# LPC11UxxMini.net
KiCad netlist of a schematic drawn in EAGLE
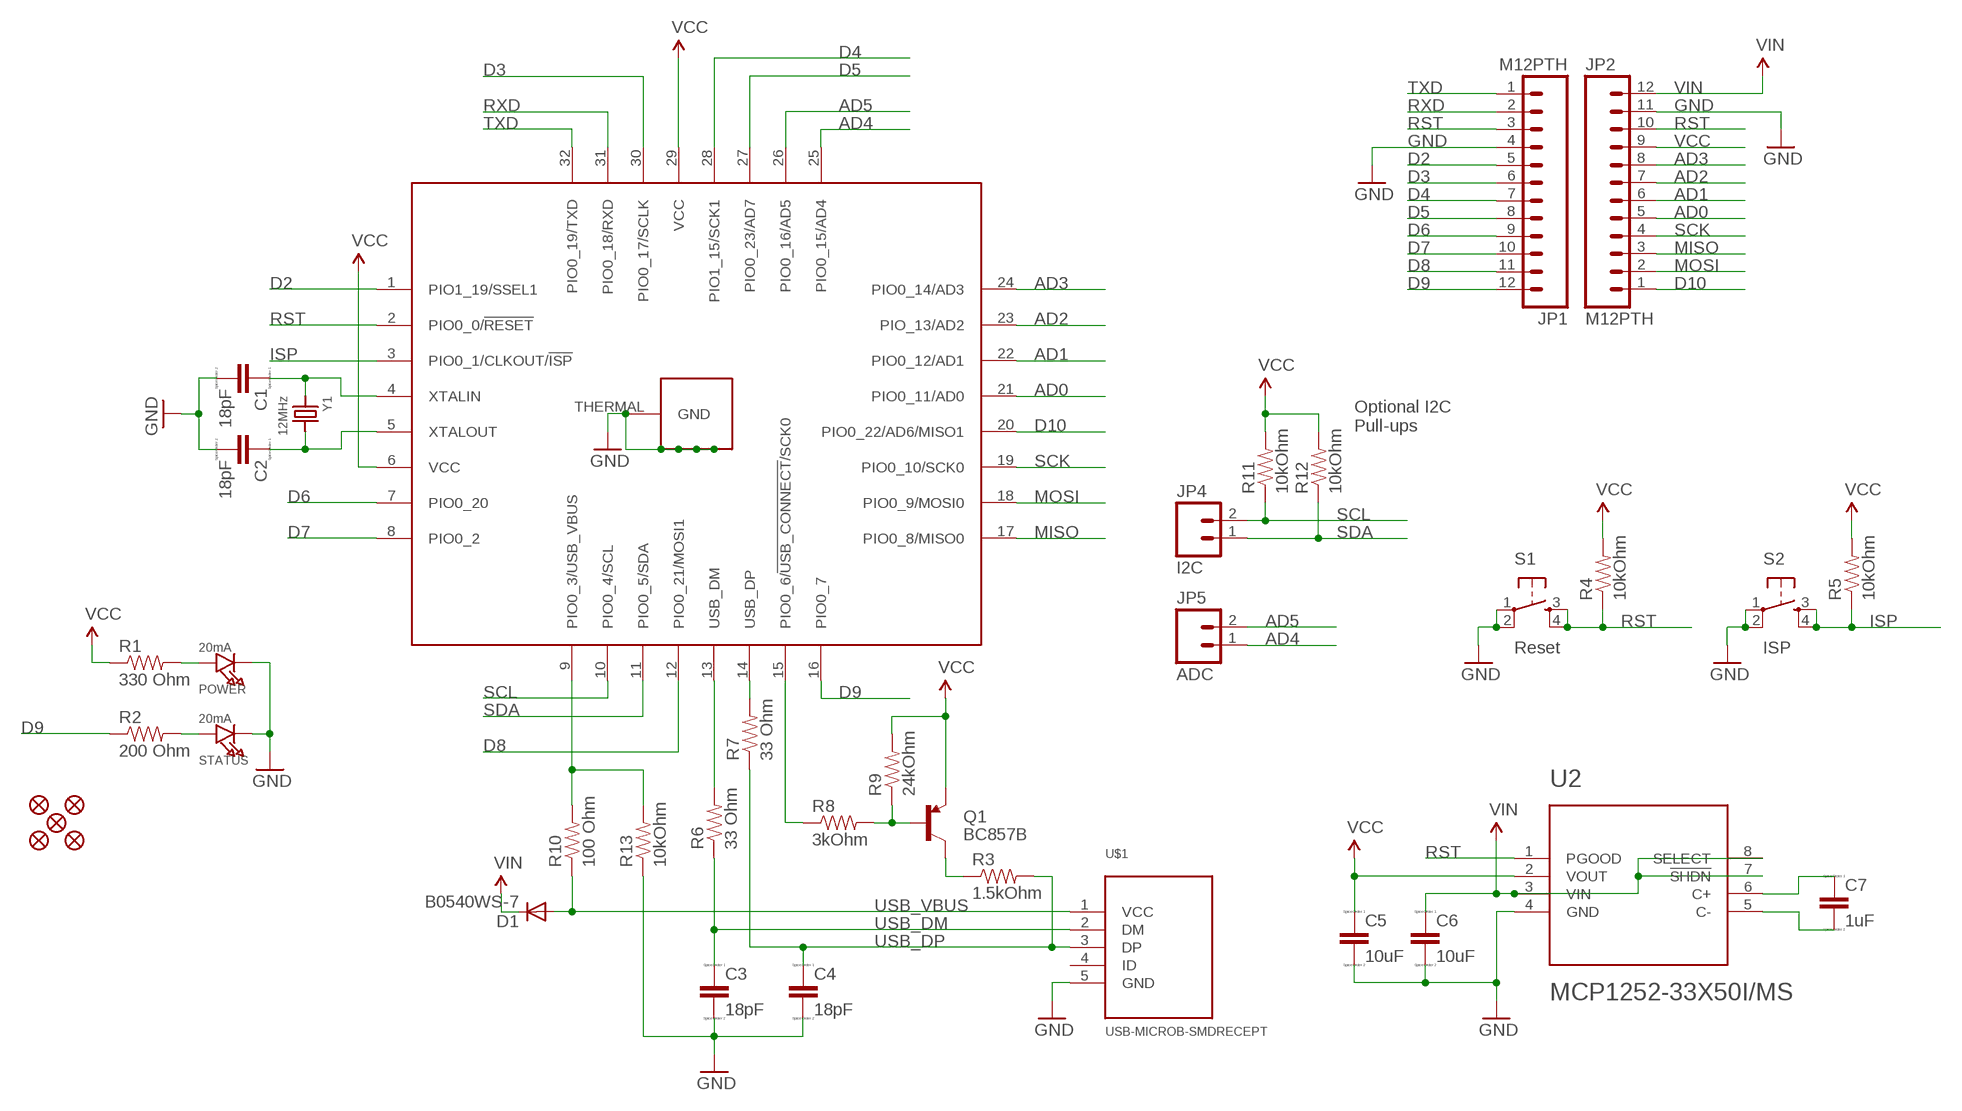
[diagram p0: schematic, sheet 1]

(export (version "E")
  (design (tool "Eeschema 10.0.6"))
  (components
    (comp (ref "C1")
      (value "18pF")
      (footprint "eagle-import:0603-CAP")
      (libsource (lib "eagle-import") (part "CAP0603-CAP"))
    )
    (comp (ref "C2")
      (value "18pF")
      (footprint "eagle-import:0603-CAP")
      (libsource (lib "eagle-import") (part "CAP0603-CAP"))
    )
    (comp (ref "C3")
      (value "18pF")
      (footprint "eagle-import:0603-CAP")
      (libsource (lib "eagle-import") (part "CAP0603-CAP"))
    )
    (comp (ref "C4")
      (value "18pF")
      (footprint "eagle-import:0603-CAP")
      (libsource (lib "eagle-import") (part "CAP0603-CAP"))
    )
    (comp (ref "C5")
      (value "10uF")
      (footprint "eagle-import:1206")
      (libsource (lib "eagle-import") (part "CAP1206"))
    )
    (comp (ref "C6")
      (value "10uF")
      (footprint "eagle-import:1206")
      (libsource (lib "eagle-import") (part "CAP1206"))
    )
    (comp (ref "C7")
      (value "1uF")
      (footprint "eagle-import:0805")
      (libsource (lib "eagle-import") (part "CAP0805"))
    )
    (comp (ref "D1")
      (value "B0540WS-7")
      (footprint "eagle-import:SOD-323")
      (libsource (lib "eagle-import") (part "DIODESOD"))
    )
    (comp (ref "JP1")
      (value "M12PTH")
      (footprint "eagle-import:1X12")
      (libsource (lib "eagle-import") (part "M12PTH"))
    )
    (comp (ref "JP2")
      (value "M12PTH")
      (footprint "eagle-import:1X12")
      (libsource (lib "eagle-import") (part "M12PTH"))
    )
    (comp (ref "JP3")
      (value "FIDUCIALUFIDUCIAL")
      (footprint "eagle-import:MICRO-FIDUCIAL")
      (libsource (lib "eagle-import") (part "FIDUCIALUFIDUCIAL"))
    )
    (comp (ref "JP4")
      (value "I2C")
      (footprint "eagle-import:1X02")
      (libsource (lib "eagle-import") (part "M02PTH"))
    )
    (comp (ref "JP5")
      (value "ADC")
      (footprint "eagle-import:1X02")
      (libsource (lib "eagle-import") (part "M02PTH"))
    )
    (comp (ref "JP6")
      (value "FIDUCIALUFIDUCIAL")
      (footprint "eagle-import:MICRO-FIDUCIAL")
      (libsource (lib "eagle-import") (part "FIDUCIALUFIDUCIAL"))
    )
    (comp (ref "JP7")
      (value "FIDUCIALUFIDUCIAL")
      (footprint "eagle-import:MICRO-FIDUCIAL")
      (libsource (lib "eagle-import") (part "FIDUCIALUFIDUCIAL"))
    )
    (comp (ref "JP8")
      (value "FIDUCIALUFIDUCIAL")
      (footprint "eagle-import:MICRO-FIDUCIAL")
      (libsource (lib "eagle-import") (part "FIDUCIALUFIDUCIAL"))
    )
    (comp (ref "JP9")
      (value "FIDUCIALUFIDUCIAL")
      (footprint "eagle-import:MICRO-FIDUCIAL")
      (libsource (lib "eagle-import") (part "FIDUCIALUFIDUCIAL"))
    )
    (comp (ref "POWER")
      (value "20mA")
      (footprint "eagle-import:CHIPLED_0603_NOOUTLINE")
      (libsource (lib "eagle-import") (part "LED0603_NOOUTLINE"))
    )
    (comp (ref "Q1")
      (value "BC857B")
      (footprint "eagle-import:SOT23-3")
      (libsource (lib "eagle-import") (part "TRANSISTOR_PNPSMD"))
    )
    (comp (ref "R1")
      (value "330 Ohm")
      (footprint "eagle-import:0402-RES")
      (libsource (lib "eagle-import") (part "RESISTOR0402-RES"))
    )
    (comp (ref "R2")
      (value "200 Ohm")
      (footprint "eagle-import:0402-RES")
      (libsource (lib "eagle-import") (part "RESISTOR0402-RES"))
    )
    (comp (ref "R3")
      (value "1.5kOhm")
      (footprint "eagle-import:0402-RES")
      (libsource (lib "eagle-import") (part "RESISTOR0402-RES"))
    )
    (comp (ref "R4")
      (value "10kOhm")
      (footprint "eagle-import:0402-RES")
      (libsource (lib "eagle-import") (part "RESISTOR0402-RES"))
    )
    (comp (ref "R5")
      (value "10kOhm")
      (footprint "eagle-import:0402-RES")
      (libsource (lib "eagle-import") (part "RESISTOR0402-RES"))
    )
    (comp (ref "R6")
      (value "33 Ohm")
      (footprint "eagle-import:0402-RES")
      (libsource (lib "eagle-import") (part "RESISTOR0402-RES"))
    )
    (comp (ref "R7")
      (value "33 Ohm")
      (footprint "eagle-import:0402-RES")
      (libsource (lib "eagle-import") (part "RESISTOR0402-RES"))
    )
    (comp (ref "R8")
      (value "3kOhm")
      (footprint "eagle-import:0402-RES")
      (libsource (lib "eagle-import") (part "RESISTOR0402-RES"))
    )
    (comp (ref "R9")
      (value "24kOhm")
      (footprint "eagle-import:0402-RES")
      (libsource (lib "eagle-import") (part "RESISTOR0402-RES"))
    )
    (comp (ref "R10")
      (value "100 Ohm")
      (footprint "eagle-import:0402-RES")
      (libsource (lib "eagle-import") (part "RESISTOR0402-RES"))
    )
    (comp (ref "R11")
      (value "10kOhm")
      (footprint "eagle-import:0402-RES")
      (libsource (lib "eagle-import") (part "RESISTOR0402-RES"))
    )
    (comp (ref "R12")
      (value "10kOhm")
      (footprint "eagle-import:0402-RES")
      (libsource (lib "eagle-import") (part "RESISTOR0402-RES"))
    )
    (comp (ref "R13")
      (value "10kOhm")
      (footprint "eagle-import:0402-RES")
      (libsource (lib "eagle-import") (part "RESISTOR0402-RES"))
    )
    (comp (ref "S1")
      (value "Reset")
      (footprint "eagle-import:TACTILE_SWITCH_SMD")
      (libsource (lib "eagle-import") (part "TAC_SWITCHSMD"))
    )
    (comp (ref "S2")
      (value "ISP")
      (footprint "eagle-import:TACTILE_SWITCH_SMD")
      (libsource (lib "eagle-import") (part "TAC_SWITCHSMD"))
    )
    (comp (ref "STATUS")
      (value "20mA")
      (footprint "eagle-import:CHIPLED_0603_NOOUTLINE")
      (libsource (lib "eagle-import") (part "LED0603_NOOUTLINE"))
    )
    (comp (ref "U$1")
      (value "USB-MICROB-SMDRECEPT")
      (footprint "eagle-import:USB-MICROB-RECEPT")
      (libsource (lib "eagle-import") (part "USB-MICROB-SMDRECEPT"))
    )
    (comp (ref "U1")
      (value "LPC11Uxx")
      (footprint "eagle-import:HVQFN32-5X5_3MMTHERMAL")
      (libsource (lib "eagle-import") (part "LPC11U2X-HVQFN33"))
    )
    (comp (ref "U2")
      (value "MCP1252-33X50I/MS")
      (footprint "eagle-import:MSOP8_0.65MM")
      (libsource (lib "eagle-import") (part "MCP1253"))
    )
    (comp (ref "Y1")
      (value "12MHz")
      (footprint "eagle-import:CRYSTAL_2.5X2")
      (libsource (lib "eagle-import") (part "CRYSTAL2.5X2.0MM"))
    )
  )
  (nets
    (net (code "1") (name "/AD0") (class "Default")
      (node (ref "JP2") (pin "5") (pinfunction "5_5") (pintype "passive"))
      (node (ref "U1") (pin "21") (pinfunction "PIO0_11/AD0_21") (pintype "bidirectional"))
    )
    (net (code "2") (name "/AD1") (class "Default")
      (node (ref "JP2") (pin "6") (pinfunction "6_6") (pintype "passive"))
      (node (ref "U1") (pin "22") (pinfunction "PIO0_12/AD1_22") (pintype "bidirectional"))
    )
    (net (code "3") (name "/AD2") (class "Default")
      (node (ref "JP2") (pin "7") (pinfunction "7_7") (pintype "passive"))
      (node (ref "U1") (pin "23") (pinfunction "PIO_13/AD2_23") (pintype "bidirectional"))
    )
    (net (code "4") (name "/AD3") (class "Default")
      (node (ref "JP2") (pin "8") (pinfunction "8_8") (pintype "passive"))
      (node (ref "U1") (pin "24") (pinfunction "PIO0_14/AD3_24") (pintype "bidirectional"))
    )
    (net (code "5") (name "/AD4") (class "Default")
      (node (ref "JP5") (pin "1") (pinfunction "1_1") (pintype "passive"))
      (node (ref "U1") (pin "25") (pinfunction "PIO0_15/AD4_25") (pintype "bidirectional"))
    )
    (net (code "6") (name "/AD5") (class "Default")
      (node (ref "JP5") (pin "2") (pinfunction "2_2") (pintype "passive"))
      (node (ref "U1") (pin "26") (pinfunction "PIO0_16/AD5_26") (pintype "bidirectional"))
    )
    (net (code "7") (name "/D2") (class "Default")
      (node (ref "JP1") (pin "5") (pinfunction "5_5") (pintype "passive"))
      (node (ref "U1") (pin "1") (pinfunction "PIO1_19/SSEL1_1") (pintype "bidirectional"))
    )
    (net (code "8") (name "/D3") (class "Default")
      (node (ref "JP1") (pin "6") (pinfunction "6_6") (pintype "passive"))
      (node (ref "U1") (pin "30") (pinfunction "PIO0_17/SCLK_30") (pintype "bidirectional"))
    )
    (net (code "9") (name "/D4") (class "Default")
      (node (ref "JP1") (pin "7") (pinfunction "7_7") (pintype "passive"))
      (node (ref "U1") (pin "28") (pinfunction "PIO1_15/SCK1_28") (pintype "bidirectional"))
    )
    (net (code "10") (name "/D5") (class "Default")
      (node (ref "JP1") (pin "8") (pinfunction "8_8") (pintype "passive"))
      (node (ref "U1") (pin "27") (pinfunction "PIO0_23/AD7_27") (pintype "bidirectional"))
    )
    (net (code "11") (name "/D6") (class "Default")
      (node (ref "JP1") (pin "9") (pinfunction "9_9") (pintype "passive"))
      (node (ref "U1") (pin "7") (pinfunction "PIO0_20_7") (pintype "bidirectional"))
    )
    (net (code "12") (name "/D7") (class "Default")
      (node (ref "JP1") (pin "10") (pinfunction "10_10") (pintype "passive"))
      (node (ref "U1") (pin "8") (pinfunction "PIO0_2_8") (pintype "bidirectional"))
    )
    (net (code "13") (name "/D8") (class "Default")
      (node (ref "JP1") (pin "11") (pinfunction "11_11") (pintype "passive"))
      (node (ref "U1") (pin "12") (pinfunction "PIO0_21/MOSI1_12") (pintype "bidirectional"))
    )
    (net (code "14") (name "/D9") (class "Default")
      (node (ref "JP1") (pin "12") (pinfunction "12_12") (pintype "passive"))
      (node (ref "R2") (pin "1") (pinfunction "1_1") (pintype "passive"))
      (node (ref "U1") (pin "16") (pinfunction "PIO0_7_16") (pintype "bidirectional"))
    )
    (net (code "15") (name "/D10") (class "Default")
      (node (ref "JP2") (pin "1") (pinfunction "1_1") (pintype "passive"))
      (node (ref "U1") (pin "20") (pinfunction "PIO0_22/AD6/MISO1_20") (pintype "bidirectional"))
    )
    (net (code "16") (name "/ISP") (class "Default")
      (node (ref "R5") (pin "1") (pinfunction "1_1") (pintype "passive"))
      (node (ref "S2") (pin "3") (pinfunction "3_3") (pintype "passive"))
      (node (ref "S2") (pin "4") (pinfunction "4_4") (pintype "passive"))
      (node (ref "U1") (pin "3") (pinfunction "PIO0_1/CLKOUT/~{ISP}_3") (pintype "bidirectional"))
    )
    (net (code "17") (name "/MISO") (class "Default")
      (node (ref "JP2") (pin "3") (pinfunction "3_3") (pintype "passive"))
      (node (ref "U1") (pin "17") (pinfunction "PIO0_8/MISO0_17") (pintype "bidirectional"))
    )
    (net (code "18") (name "/MOSI") (class "Default")
      (node (ref "JP2") (pin "2") (pinfunction "2_2") (pintype "passive"))
      (node (ref "U1") (pin "18") (pinfunction "PIO0_9/MOSI0_18") (pintype "bidirectional"))
    )
    (net (code "19") (name "/RST") (class "Default")
      (node (ref "JP1") (pin "3") (pinfunction "3_3") (pintype "passive"))
      (node (ref "JP2") (pin "10") (pinfunction "10_10") (pintype "passive"))
      (node (ref "R4") (pin "1") (pinfunction "1_1") (pintype "passive"))
      (node (ref "S1") (pin "3") (pinfunction "3_3") (pintype "passive"))
      (node (ref "S1") (pin "4") (pinfunction "4_4") (pintype "passive"))
      (node (ref "U1") (pin "2") (pinfunction "PIO0_0/~{RESET}_2") (pintype "bidirectional"))
      (node (ref "U2") (pin "1") (pinfunction "PGOOD_1") (pintype "bidirectional"))
    )
    (net (code "20") (name "/RXD") (class "Default")
      (node (ref "JP1") (pin "2") (pinfunction "2_2") (pintype "passive"))
      (node (ref "U1") (pin "31") (pinfunction "PIO0_18/RXD_31") (pintype "bidirectional"))
    )
    (net (code "21") (name "/SCK") (class "Default")
      (node (ref "JP2") (pin "4") (pinfunction "4_4") (pintype "passive"))
      (node (ref "U1") (pin "19") (pinfunction "PIO0_10/SCK0_19") (pintype "bidirectional"))
    )
    (net (code "22") (name "/SCL") (class "Default")
      (node (ref "JP4") (pin "2") (pinfunction "2_2") (pintype "passive"))
      (node (ref "R11") (pin "1") (pinfunction "1_1") (pintype "passive"))
      (node (ref "U1") (pin "10") (pinfunction "PIO0_4/SCL_10") (pintype "bidirectional"))
    )
    (net (code "23") (name "/SDA") (class "Default")
      (node (ref "JP4") (pin "1") (pinfunction "1_1") (pintype "passive"))
      (node (ref "R12") (pin "1") (pinfunction "1_1") (pintype "passive"))
      (node (ref "U1") (pin "11") (pinfunction "PIO0_5/SDA_11") (pintype "bidirectional"))
    )
    (net (code "24") (name "/TXD") (class "Default")
      (node (ref "JP1") (pin "1") (pinfunction "1_1") (pintype "passive"))
      (node (ref "U1") (pin "32") (pinfunction "PIO0_19/TXD_32") (pintype "bidirectional"))
    )
    (net (code "25") (name "/USB_DM") (class "Default")
      (node (ref "C3") (pin "1") (pinfunction "1_1") (pintype "passive"))
      (node (ref "R6") (pin "1") (pinfunction "1_1") (pintype "passive"))
      (node (ref "U$1") (pin "2") (pinfunction "DM_2") (pintype "bidirectional"))
    )
    (net (code "26") (name "/USB_DP") (class "Default")
      (node (ref "C4") (pin "1") (pinfunction "1_1") (pintype "passive"))
      (node (ref "R3") (pin "2") (pinfunction "2_2") (pintype "passive"))
      (node (ref "R7") (pin "1") (pinfunction "1_1") (pintype "passive"))
      (node (ref "U$1") (pin "3") (pinfunction "DP_3") (pintype "bidirectional"))
    )
    (net (code "27") (name "/USB_VBUS") (class "Default")
      (node (ref "D1") (pin "2") (pinfunction "A_2") (pintype "passive"))
      (node (ref "R10") (pin "1") (pinfunction "1_1") (pintype "passive"))
      (node (ref "U$1") (pin "1") (pinfunction "VCC_1") (pintype "bidirectional"))
    )
    (net (code "28") (name "GND") (class "Default")
      (node (ref "C1") (pin "2") (pinfunction "2_2") (pintype "passive"))
      (node (ref "C2") (pin "2") (pinfunction "2_2") (pintype "passive"))
      (node (ref "C3") (pin "2") (pinfunction "2_2") (pintype "passive"))
      (node (ref "C4") (pin "2") (pinfunction "2_2") (pintype "passive"))
      (node (ref "C5") (pin "2") (pinfunction "2_2") (pintype "passive"))
      (node (ref "C6") (pin "2") (pinfunction "2_2") (pintype "passive"))
      (node (ref "JP1") (pin "4") (pinfunction "4_4") (pintype "passive"))
      (node (ref "JP2") (pin "11") (pinfunction "11_11") (pintype "passive"))
      (node (ref "POWER") (pin "C") (pinfunction "C_C") (pintype "passive"))
      (node (ref "R13") (pin "1") (pinfunction "1_1") (pintype "passive"))
      (node (ref "S1") (pin "1") (pinfunction "1_1") (pintype "passive"))
      (node (ref "S1") (pin "2") (pinfunction "2_2") (pintype "passive"))
      (node (ref "S2") (pin "1") (pinfunction "1_1") (pintype "passive"))
      (node (ref "S2") (pin "2") (pinfunction "2_2") (pintype "passive"))
      (node (ref "STATUS") (pin "C") (pinfunction "C_C") (pintype "passive"))
      (node (ref "U$1") (pin "5") (pinfunction "GND_5") (pintype "bidirectional"))
      (node (ref "U1") (pin "THERMAL") (pinfunction "GND_THERMAL") (pintype "bidirectional"))
      (node (ref "U1") (pin "THERMAL@1") (pinfunction "GND_THERMAL@1") (pintype "bidirectional"))
      (node (ref "U1") (pin "THERMAL@2") (pinfunction "GND_THERMAL@2") (pintype "bidirectional"))
      (node (ref "U1") (pin "THERMAL@3") (pinfunction "GND_THERMAL@3") (pintype "bidirectional"))
      (node (ref "U1") (pin "THERMAL@4") (pinfunction "GND_THERMAL@4") (pintype "bidirectional"))
      (node (ref "U2") (pin "4") (pinfunction "GND_4") (pintype "bidirectional"))
    )
    (net (code "29") (name "Net-(POWER-PadA)") (class "Default")
      (node (ref "POWER") (pin "A") (pinfunction "A_A") (pintype "passive"))
      (node (ref "R1") (pin "2") (pinfunction "2_2") (pintype "passive"))
    )
    (net (code "30") (name "Net-(Q1-B)") (class "Default")
      (node (ref "Q1") (pin "1") (pinfunction "B_1") (pintype "passive"))
      (node (ref "R8") (pin "2") (pinfunction "2_2") (pintype "passive"))
      (node (ref "R9") (pin "1") (pinfunction "1_1") (pintype "passive"))
    )
    (net (code "31") (name "Net-(Q1-C)") (class "Default")
      (node (ref "Q1") (pin "3") (pinfunction "C_3") (pintype "passive"))
      (node (ref "R3") (pin "1") (pinfunction "1_1") (pintype "passive"))
    )
    (net (code "32") (name "Net-(R2-Pad2)") (class "Default")
      (node (ref "R2") (pin "2") (pinfunction "2_2") (pintype "passive"))
      (node (ref "STATUS") (pin "A") (pinfunction "A_A") (pintype "passive"))
    )
    (net (code "33") (name "Net-(U1-PIO0_3{slash}USB_VBUS)") (class "Default")
      (node (ref "R10") (pin "2") (pinfunction "2_2") (pintype "passive"))
      (node (ref "R13") (pin "2") (pinfunction "2_2") (pintype "passive"))
      (node (ref "U1") (pin "9") (pinfunction "PIO0_3/USB_VBUS_9") (pintype "bidirectional"))
    )
    (net (code "34") (name "Net-(U1-PIO0_6{slash}~{USB_CONNECT}{slash}SCK0)") (class "Default")
      (node (ref "R8") (pin "1") (pinfunction "1_1") (pintype "passive"))
      (node (ref "U1") (pin "15") (pinfunction "PIO0_6/~{USB_CONNECT}/SCK0_15") (pintype "bidirectional"))
    )
    (net (code "35") (name "Net-(U1-USB_DM)") (class "Default")
      (node (ref "R6") (pin "2") (pinfunction "2_2") (pintype "passive"))
      (node (ref "U1") (pin "13") (pinfunction "USB_DM_13") (pintype "bidirectional"))
    )
    (net (code "36") (name "Net-(U1-USB_DP)") (class "Default")
      (node (ref "R7") (pin "2") (pinfunction "2_2") (pintype "passive"))
      (node (ref "U1") (pin "14") (pinfunction "USB_DP_14") (pintype "bidirectional"))
    )
    (net (code "37") (name "Net-(U1-XTALIN)") (class "Default")
      (node (ref "C1") (pin "1") (pinfunction "1_1") (pintype "passive"))
      (node (ref "U1") (pin "4") (pinfunction "XTALIN_4") (pintype "bidirectional"))
      (node (ref "Y1") (pin "1") (pinfunction "1_1") (pintype "passive"))
    )
    (net (code "38") (name "Net-(U1-XTALOUT)") (class "Default")
      (node (ref "C2") (pin "1") (pinfunction "1_1") (pintype "passive"))
      (node (ref "U1") (pin "5") (pinfunction "XTALOUT_5") (pintype "bidirectional"))
      (node (ref "Y1") (pin "3") (pinfunction "2_3") (pintype "passive"))
    )
    (net (code "39") (name "Net-(U2-C+)") (class "Default")
      (node (ref "C7") (pin "1") (pinfunction "1_1") (pintype "passive"))
      (node (ref "U2") (pin "6") (pinfunction "C+_6") (pintype "bidirectional"))
    )
    (net (code "40") (name "Net-(U2-C-)") (class "Default")
      (node (ref "C7") (pin "2") (pinfunction "2_2") (pintype "passive"))
      (node (ref "U2") (pin "5") (pinfunction "C-_5") (pintype "bidirectional"))
    )
    (net (code "41") (name "VCC") (class "Default")
      (node (ref "C5") (pin "1") (pinfunction "1_1") (pintype "passive"))
      (node (ref "JP2") (pin "9") (pinfunction "9_9") (pintype "passive"))
      (node (ref "Q1") (pin "2") (pinfunction "E_2") (pintype "passive"))
      (node (ref "R1") (pin "1") (pinfunction "1_1") (pintype "passive"))
      (node (ref "R11") (pin "2") (pinfunction "2_2") (pintype "passive"))
      (node (ref "R12") (pin "2") (pinfunction "2_2") (pintype "passive"))
      (node (ref "R4") (pin "2") (pinfunction "2_2") (pintype "passive"))
      (node (ref "R5") (pin "2") (pinfunction "2_2") (pintype "passive"))
      (node (ref "R9") (pin "2") (pinfunction "2_2") (pintype "passive"))
      (node (ref "U1") (pin "29") (pinfunction "VCC_29") (pintype "bidirectional"))
      (node (ref "U1") (pin "6") (pinfunction "VCC_6") (pintype "bidirectional"))
      (node (ref "U2") (pin "2") (pinfunction "VOUT_2") (pintype "bidirectional"))
    )
    (net (code "42") (name "VIN") (class "Default")
      (node (ref "C6") (pin "1") (pinfunction "1_1") (pintype "passive"))
      (node (ref "D1") (pin "1") (pinfunction "C_1") (pintype "passive"))
      (node (ref "JP2") (pin "12") (pinfunction "12_12") (pintype "passive"))
      (node (ref "U2") (pin "3") (pinfunction "VIN_3") (pintype "bidirectional"))
      (node (ref "U2") (pin "7") (pinfunction "~{SHDN}_7") (pintype "bidirectional"))
      (node (ref "U2") (pin "8") (pinfunction "SELECT_8") (pintype "bidirectional"))
    )
    (net (code "43") (name "unconnected-(U$1-ID-Pad4)") (class "Default")
      (node (ref "U$1") (pin "4") (pinfunction "ID_4") (pintype "bidirectional"))
    )
  )
)
